# Programmable_Stage.net
KiCad netlist of a schematic drawn in Altium Designer
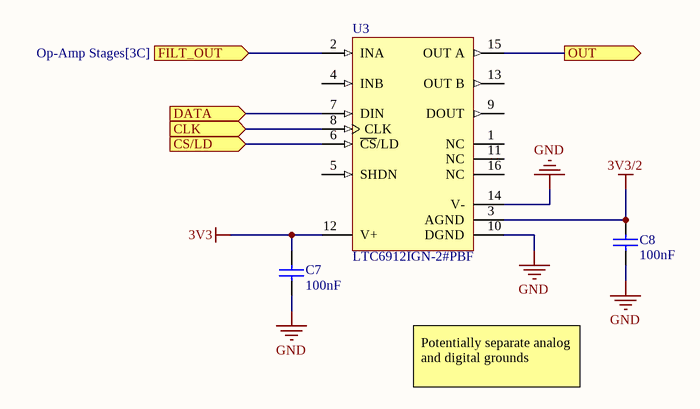
[diagram p0: Programmable Stage.SchDoc]

(export (version "E")
  (design (tool "Eeschema 10.0.6"))
  (components
    (comp (ref "C7")
      (value "100nF")
      (footprint "RAD-0.3")
      (description "Capacitor")
      (fields (field (name "PUBLISHER") "Altium Limited"))
      (libsource (lib "Miscellaneous Devices") (part "Cap"))
    )
    (comp (ref "C8")
      (value "100nF")
      (footprint "RAD-0.3")
      (description "Capacitor")
      (fields (field (name "PUBLISHER") "Altium Limited"))
      (libsource (lib "Miscellaneous Devices") (part "Cap"))
    )
    (comp (ref "U3")
      (value "LTC6912IGN-2#PBF")
      (footprint "LT-GN-16_L")
      (fields
        (field (name "MANUFACTURER") "Linear Technology")
        (field (name "LINEAR TECHNOLOGY PART NUMBER") "LTC6912-2")
      )
      (libsource (lib "Altium Content Vault") (part "LT-LTC6912-2-GN-16"))
    )
  )
  (nets
    (net (code "1") (name "/CLK") (class "Default")
      (node (ref "U3") (pin "8") (pinfunction "CLK_8") (pintype "input"))
    )
    (net (code "2") (name "/CS{slash}LD") (class "Default")
      (node (ref "U3") (pin "6") (pinfunction "~{CS}/LD_6") (pintype "input"))
    )
    (net (code "3") (name "/DATA") (class "Default")
      (node (ref "U3") (pin "7") (pinfunction "DIN_7") (pintype "input"))
    )
    (net (code "4") (name "/FILT_OUT") (class "Default")
      (node (ref "U3") (pin "2") (pinfunction "INA_2") (pintype "input"))
    )
    (net (code "5") (name "/OUT") (class "Default")
      (node (ref "U3") (pin "15") (pinfunction "OUT_A_15") (pintype "output"))
    )
    (net (code "6") (name "3V3") (class "Default")
      (node (ref "C7") (pin "2") (pinfunction "2_2") (pintype "passive"))
      (node (ref "U3") (pin "12") (pinfunction "V+_12") (pintype "power_in"))
    )
    (net (code "7") (name "3V3{slash}2") (class "Default")
      (node (ref "C8") (pin "2") (pinfunction "2_2") (pintype "passive"))
      (node (ref "U3") (pin "3") (pinfunction "AGND_3") (pintype "power_in"))
    )
    (net (code "8") (name "GND") (class "Default")
      (node (ref "C7") (pin "1") (pinfunction "1_1") (pintype "passive"))
      (node (ref "C8") (pin "1") (pinfunction "1_1") (pintype "passive"))
      (node (ref "U3") (pin "10") (pinfunction "DGND_10") (pintype "power_in"))
      (node (ref "U3") (pin "14") (pinfunction "V-_14") (pintype "power_in"))
    )
    (net (code "9") (name "unconnected-(U3-DOUT-Pad9)") (class "Default")
      (node (ref "U3") (pin "9") (pinfunction "DOUT_9") (pintype "output"))
    )
    (net (code "10") (name "unconnected-(U3-INB-Pad4)") (class "Default")
      (node (ref "U3") (pin "4") (pinfunction "INB_4") (pintype "input"))
    )
    (net (code "11") (name "unconnected-(U3-NC-Pad1)") (class "Default")
      (node (ref "U3") (pin "1") (pinfunction "NC_1") (pintype "passive"))
    )
    (net (code "12") (name "unconnected-(U3-NC-Pad11)") (class "Default")
      (node (ref "U3") (pin "11") (pinfunction "NC_11") (pintype "passive"))
    )
    (net (code "13") (name "unconnected-(U3-NC-Pad16)") (class "Default")
      (node (ref "U3") (pin "16") (pinfunction "NC_16") (pintype "passive"))
    )
    (net (code "14") (name "unconnected-(U3-OUT_B-Pad13)") (class "Default")
      (node (ref "U3") (pin "13") (pinfunction "OUT_B_13") (pintype "output"))
    )
    (net (code "15") (name "unconnected-(U3-SHDN-Pad5)") (class "Default")
      (node (ref "U3") (pin "5") (pinfunction "SHDN_5") (pintype "input"))
    )
  )
)
